# NB2_CommonMemory_Termination.net
KiCad netlist of a schematic drawn in Altium Designer
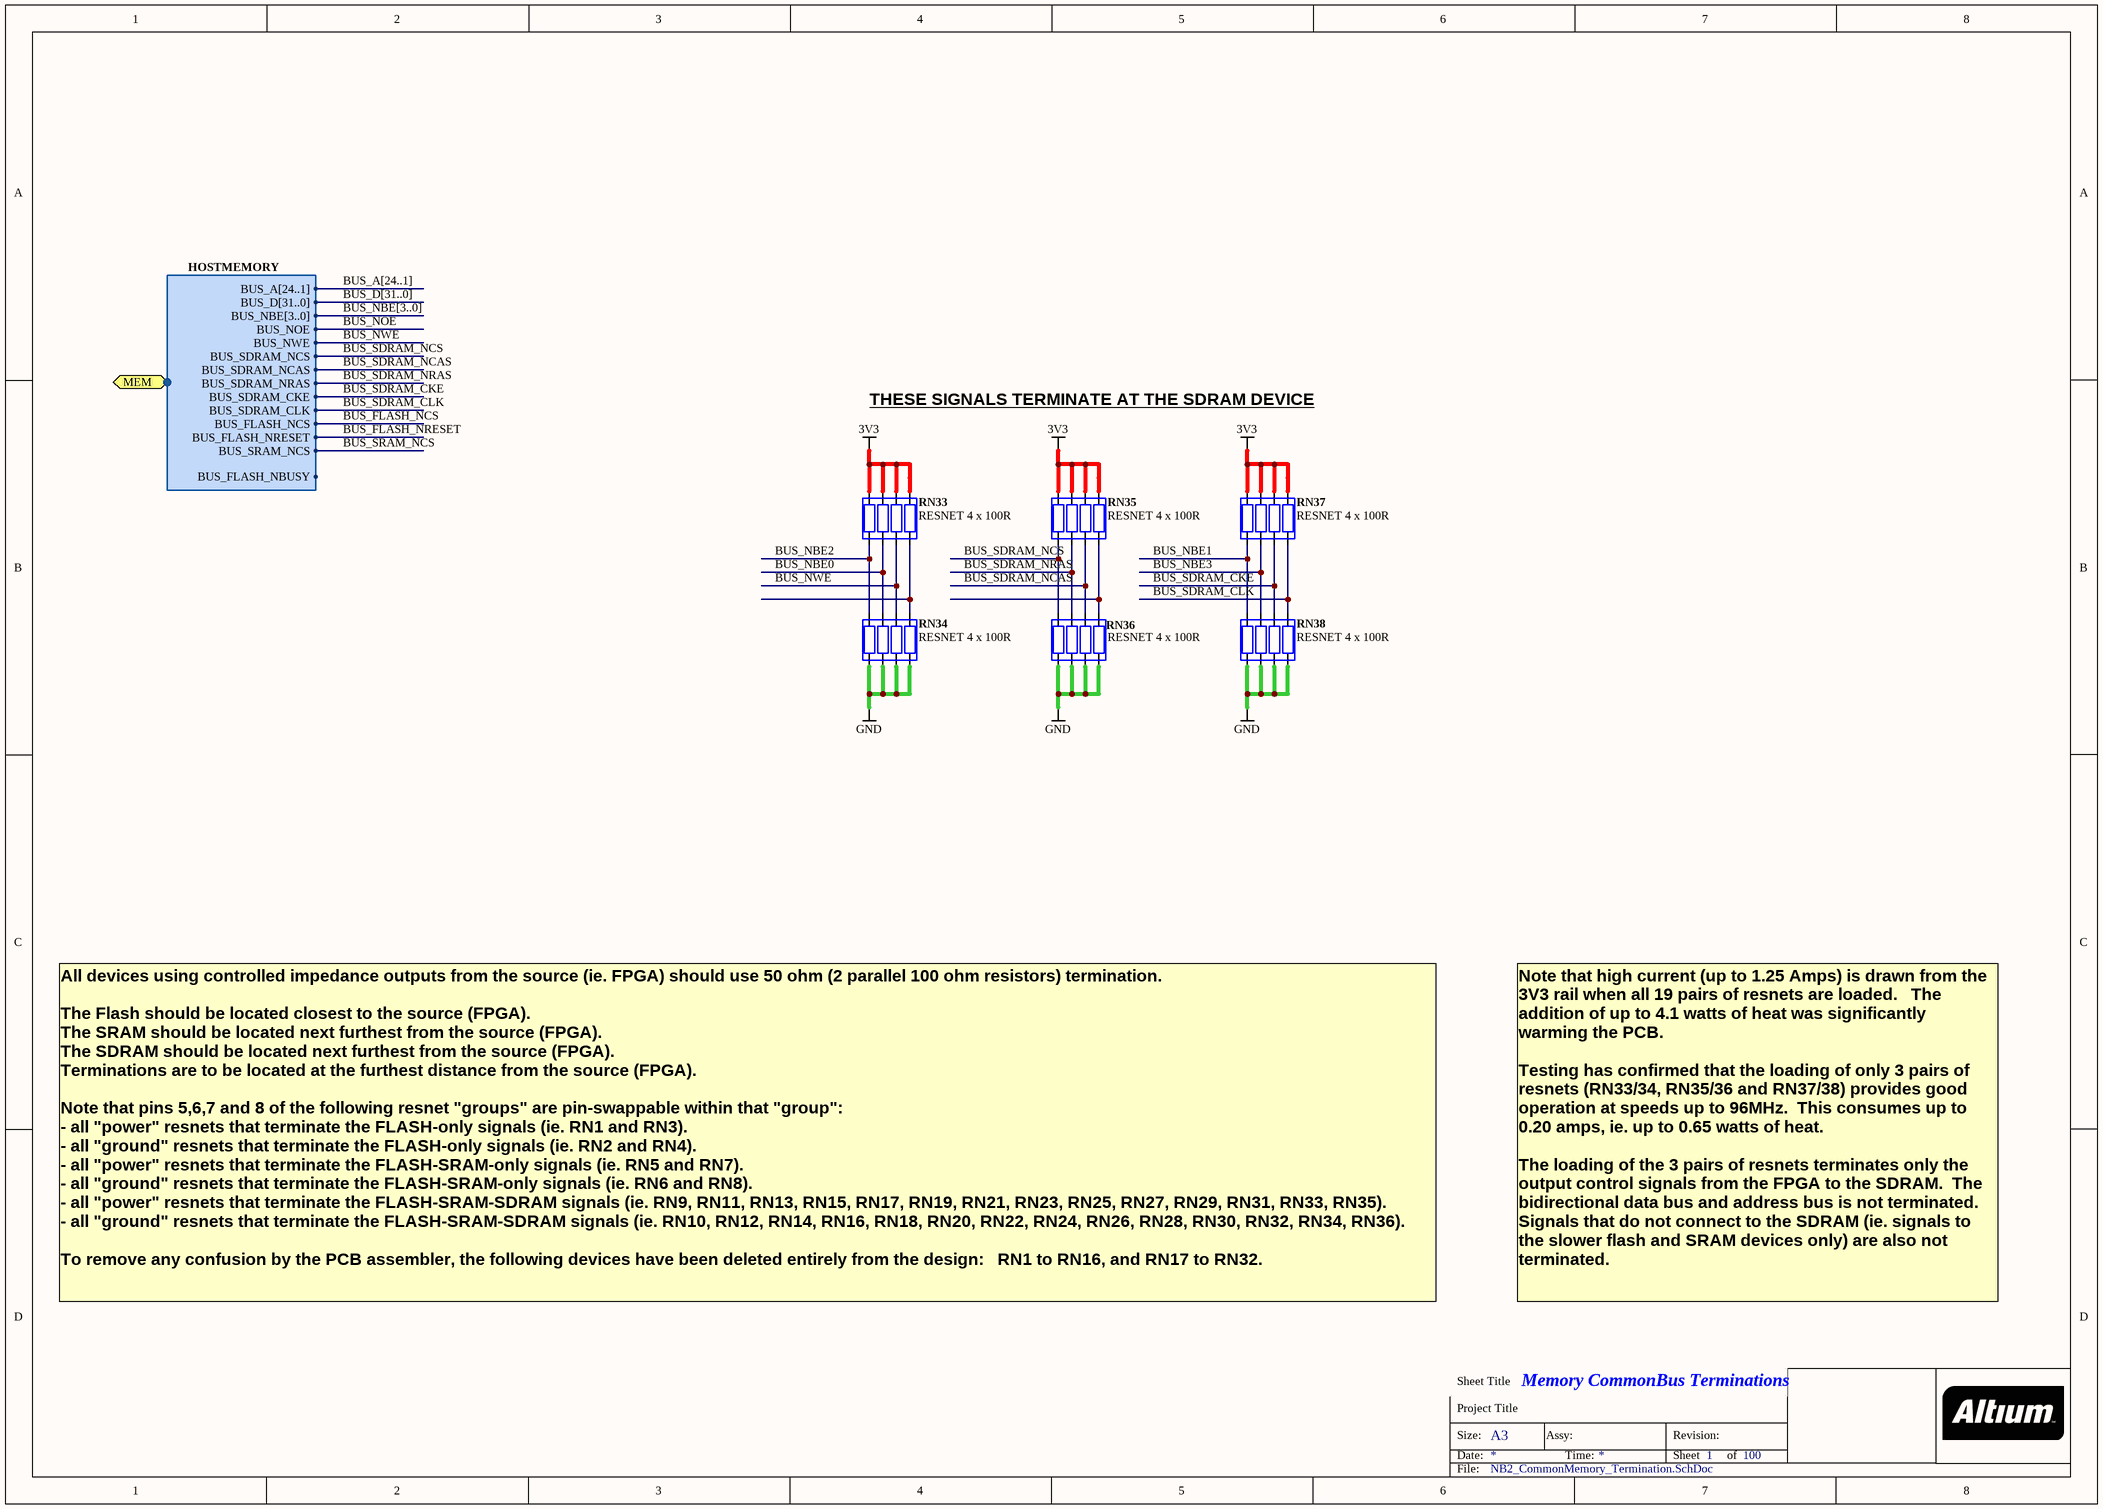
[diagram p0: NB2_CommonMemory_Termination.SchDoc]

(export (version "E")
  (design (tool "Eeschema 10.0.6"))
  (components
    (comp (ref "RN33")
      (value "RESNET 4 x 100R")
      (footprint "RESNET-1005X4")
      (description "Resistor Network, Isolated, 4 x 100R, 5%, SMD 0402 x 4")
      (fields (field (name "TOLERANCE") "5 %"))
      (libsource (lib "AltiumDesignLibrary") (part "RES-NET-IND-4-SMD"))
    )
    (comp (ref "RN34")
      (value "RESNET 4 x 100R")
      (footprint "RESNET-1005X4")
      (description "Resistor Network, Isolated, 4 x 100R, 5%, SMD 0402 x 4")
      (fields (field (name "TOLERANCE") "5 %"))
      (libsource (lib "AltiumDesignLibrary") (part "RES-NET-IND-4-SMD"))
    )
    (comp (ref "RN35")
      (value "RESNET 4 x 100R")
      (footprint "RESNET-1005X4")
      (description "Resistor Network, Isolated, 4 x 100R, 5%, SMD 0402 x 4")
      (fields (field (name "TOLERANCE") "5 %"))
      (libsource (lib "AltiumDesignLibrary") (part "RES-NET-IND-4-SMD"))
    )
    (comp (ref "RN36")
      (value "RESNET 4 x 100R")
      (footprint "RESNET-1005X4")
      (description "Resistor Network, Isolated, 4 x 100R, 5%, SMD 0402 x 4")
      (fields (field (name "TOLERANCE") "5 %"))
      (libsource (lib "AltiumDesignLibrary") (part "RES-NET-IND-4-SMD"))
    )
    (comp (ref "RN37")
      (value "RESNET 4 x 100R")
      (footprint "RESNET-1005X4")
      (description "Resistor Network, Isolated, 4 x 100R, 5%, SMD 0402 x 4")
      (fields (field (name "TOLERANCE") "5 %"))
      (libsource (lib "AltiumDesignLibrary") (part "RES-NET-IND-4-SMD"))
    )
    (comp (ref "RN38")
      (value "RESNET 4 x 100R")
      (footprint "RESNET-1005X4")
      (description "Resistor Network, Isolated, 4 x 100R, 5%, SMD 0402 x 4")
      (fields (field (name "TOLERANCE") "5 %"))
      (libsource (lib "AltiumDesignLibrary") (part "RES-NET-IND-4-SMD"))
    )
  )
  (nets
    (net (code "62") (name "/BUS_NBE0") (class "Default")
      (node (ref "RN33") (pin "6") (pinfunction "6_6") (pintype "passive"))
      (node (ref "RN34") (pin "7") (pinfunction "7_7") (pintype "passive"))
    )
    (net (code "63") (name "/BUS_NBE1") (class "Default")
      (node (ref "RN37") (pin "5") (pinfunction "5_5") (pintype "passive"))
      (node (ref "RN38") (pin "8") (pinfunction "8_8") (pintype "passive"))
    )
    (net (code "64") (name "/BUS_NBE2") (class "Default")
      (node (ref "RN33") (pin "5") (pinfunction "5_5") (pintype "passive"))
      (node (ref "RN34") (pin "8") (pinfunction "8_8") (pintype "passive"))
    )
    (net (code "65") (name "/BUS_NBE3") (class "Default")
      (node (ref "RN37") (pin "6") (pinfunction "6_6") (pintype "passive"))
      (node (ref "RN38") (pin "7") (pinfunction "7_7") (pintype "passive"))
    )
    (net (code "67") (name "/BUS_NWE") (class "Default")
      (node (ref "RN33") (pin "7") (pinfunction "7_7") (pintype "passive"))
      (node (ref "RN34") (pin "6") (pinfunction "6_6") (pintype "passive"))
    )
    (net (code "68") (name "/BUS_SDRAM_CKE") (class "Default")
      (node (ref "RN37") (pin "7") (pinfunction "7_7") (pintype "passive"))
      (node (ref "RN38") (pin "6") (pinfunction "6_6") (pintype "passive"))
    )
    (net (code "69") (name "/BUS_SDRAM_CLK") (class "Default")
      (node (ref "RN37") (pin "8") (pinfunction "8_8") (pintype "passive"))
      (node (ref "RN38") (pin "5") (pinfunction "5_5") (pintype "passive"))
    )
    (net (code "70") (name "/BUS_SDRAM_NCAS") (class "Default")
      (node (ref "RN35") (pin "7") (pinfunction "7_7") (pintype "passive"))
      (node (ref "RN36") (pin "6") (pinfunction "6_6") (pintype "passive"))
    )
    (net (code "71") (name "/BUS_SDRAM_NCS") (class "Default")
      (node (ref "RN35") (pin "5") (pinfunction "5_5") (pintype "passive"))
      (node (ref "RN36") (pin "8") (pinfunction "8_8") (pintype "passive"))
    )
    (net (code "72") (name "/BUS_SDRAM_NRAS") (class "Default")
      (node (ref "RN35") (pin "6") (pinfunction "6_6") (pintype "passive"))
      (node (ref "RN36") (pin "7") (pinfunction "7_7") (pintype "passive"))
    )
    (net (code "76") (name "3V3") (class "Default")
      (node (ref "RN33") (pin "1") (pinfunction "1_1") (pintype "passive"))
      (node (ref "RN33") (pin "2") (pinfunction "2_2") (pintype "passive"))
      (node (ref "RN33") (pin "3") (pinfunction "3_3") (pintype "passive"))
      (node (ref "RN33") (pin "4") (pinfunction "4_4") (pintype "passive"))
      (node (ref "RN35") (pin "1") (pinfunction "1_1") (pintype "passive"))
      (node (ref "RN35") (pin "2") (pinfunction "2_2") (pintype "passive"))
      (node (ref "RN35") (pin "3") (pinfunction "3_3") (pintype "passive"))
      (node (ref "RN35") (pin "4") (pinfunction "4_4") (pintype "passive"))
      (node (ref "RN37") (pin "1") (pinfunction "1_1") (pintype "passive"))
      (node (ref "RN37") (pin "2") (pinfunction "2_2") (pintype "passive"))
      (node (ref "RN37") (pin "3") (pinfunction "3_3") (pintype "passive"))
      (node (ref "RN37") (pin "4") (pinfunction "4_4") (pintype "passive"))
    )
    (net (code "77") (name "GND") (class "Default")
      (node (ref "RN34") (pin "1") (pinfunction "1_1") (pintype "passive"))
      (node (ref "RN34") (pin "2") (pinfunction "2_2") (pintype "passive"))
      (node (ref "RN34") (pin "3") (pinfunction "3_3") (pintype "passive"))
      (node (ref "RN34") (pin "4") (pinfunction "4_4") (pintype "passive"))
      (node (ref "RN36") (pin "1") (pinfunction "1_1") (pintype "passive"))
      (node (ref "RN36") (pin "2") (pinfunction "2_2") (pintype "passive"))
      (node (ref "RN36") (pin "3") (pinfunction "3_3") (pintype "passive"))
      (node (ref "RN36") (pin "4") (pinfunction "4_4") (pintype "passive"))
      (node (ref "RN38") (pin "1") (pinfunction "1_1") (pintype "passive"))
      (node (ref "RN38") (pin "2") (pinfunction "2_2") (pintype "passive"))
      (node (ref "RN38") (pin "3") (pinfunction "3_3") (pintype "passive"))
      (node (ref "RN38") (pin "4") (pinfunction "4_4") (pintype "passive"))
    )
    (net (code "78") (name "Net-(RN33-Pad8)") (class "Default")
      (node (ref "RN33") (pin "8") (pinfunction "8_8") (pintype "passive"))
      (node (ref "RN34") (pin "5") (pinfunction "5_5") (pintype "passive"))
    )
    (net (code "79") (name "Net-(RN35-Pad8)") (class "Default")
      (node (ref "RN35") (pin "8") (pinfunction "8_8") (pintype "passive"))
      (node (ref "RN36") (pin "5") (pinfunction "5_5") (pintype "passive"))
    )
  )
)
